# 04-AT86RF215IQ.net
KiCad netlist of a schematic drawn in Altium Designer
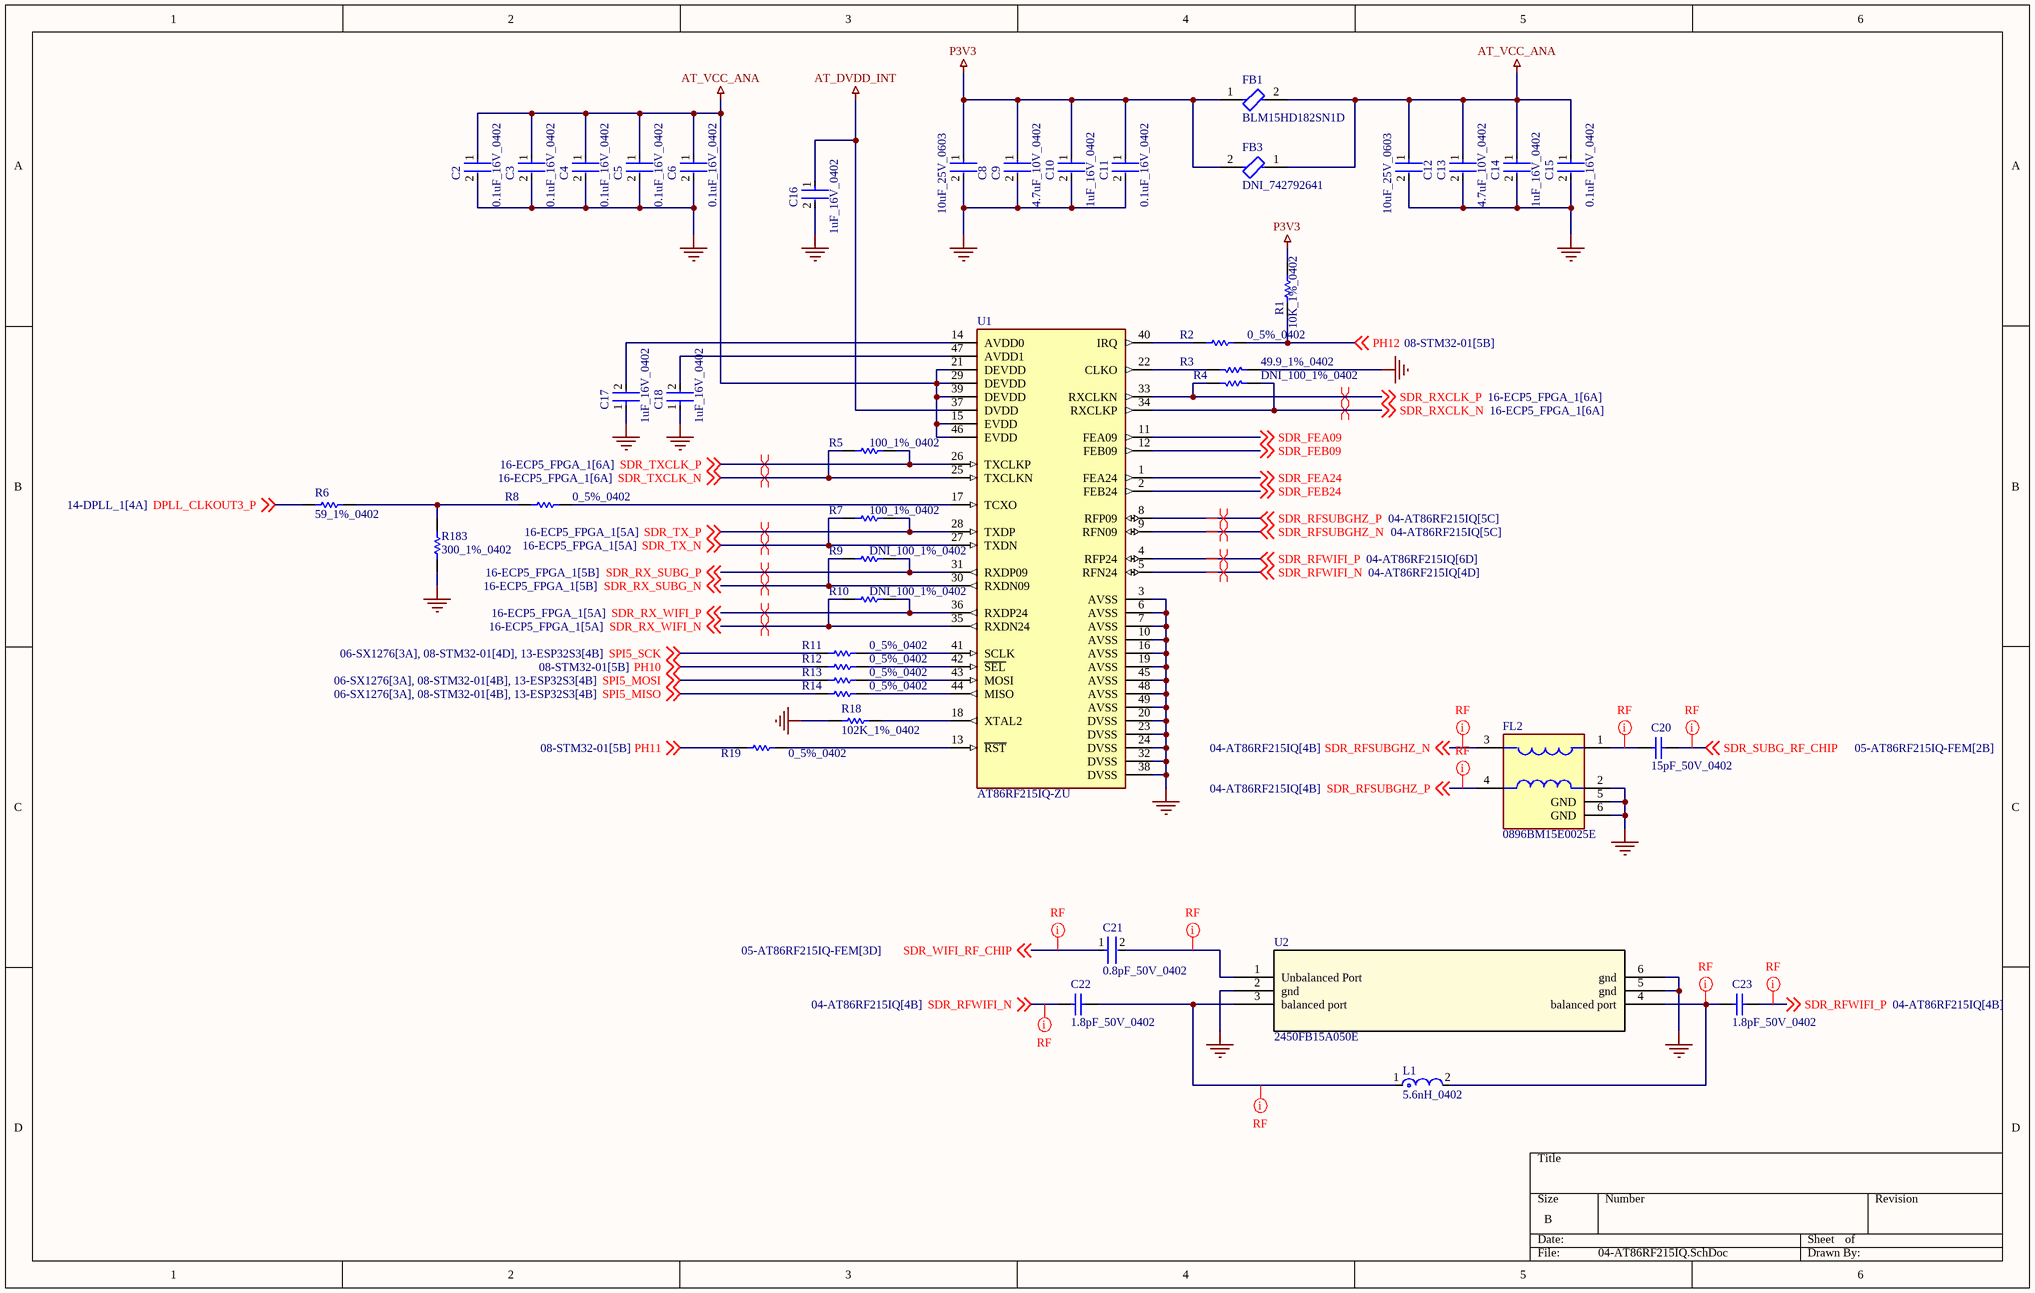
[diagram p0: 04-AT86RF215IQ.SchDoc]

(export (version "E")
  (design (tool "Eeschema 10.0.6"))
  (components
    (comp (ref "C2")
      (value "0.1uF_16V_0402")
      (footprint "FP-C0402-BB-MFG")
      (description "CAP CER 0.1UF 16V 5% X7R 0402")
      (fields
        (field (name "MANUFACTURER") "Kemet")
        (field (name "MANUFACTURER PART NUMBER") "C0402C104J4RACTU")
      )
      (libsource (lib "Altium Content Vault") (part "b4654b650e69147ec39a6b967a45e02"))
    )
    (comp (ref "C3")
      (value "0.1uF_16V_0402")
      (footprint "FP-C0402-BB-MFG")
      (description "CAP CER 0.1UF 16V 5% X7R 0402")
      (fields
        (field (name "MANUFACTURER") "Kemet")
        (field (name "MANUFACTURER PART NUMBER") "C0402C104J4RACTU")
      )
      (libsource (lib "Altium Content Vault") (part "b4654b650e69147ec39a6b967a45e02"))
    )
    (comp (ref "C4")
      (value "0.1uF_16V_0402")
      (footprint "FP-C0402-BB-MFG")
      (description "CAP CER 0.1UF 16V 5% X7R 0402")
      (fields
        (field (name "MANUFACTURER") "Kemet")
        (field (name "MANUFACTURER PART NUMBER") "C0402C104J4RACTU")
      )
      (libsource (lib "Altium Content Vault") (part "b4654b650e69147ec39a6b967a45e02"))
    )
    (comp (ref "C5")
      (value "0.1uF_16V_0402")
      (footprint "FP-C0402-BB-MFG")
      (description "CAP CER 0.1UF 16V 5% X7R 0402")
      (fields
        (field (name "MANUFACTURER") "Kemet")
        (field (name "MANUFACTURER PART NUMBER") "C0402C104J4RACTU")
      )
      (libsource (lib "Altium Content Vault") (part "b4654b650e69147ec39a6b967a45e02"))
    )
    (comp (ref "C6")
      (value "0.1uF_16V_0402")
      (footprint "FP-C0402-BB-MFG")
      (description "CAP CER 0.1UF 16V 5% X7R 0402")
      (fields
        (field (name "MANUFACTURER") "Kemet")
        (field (name "MANUFACTURER PART NUMBER") "C0402C104J4RACTU")
      )
      (libsource (lib "Altium Content Vault") (part "b4654b650e69147ec39a6b967a45e02"))
    )
    (comp (ref "C8")
      (value "10uF_25V_0603")
      (footprint "FP-CL10-IPC_C")
      (description "Cap Ceramic 10uF 25V X5R ±20% Pad SMD 0603 +85°C T/R")
      (fields (field (name "TOLERANCE") "20%"))
      (libsource (lib "Altium Content Vault") (part "b4654b650e69147ec39a6b967a45e02"))
    )
    (comp (ref "C9")
      (value "4.7uF_10V_0402")
      (footprint "FP-C1005-050-0_15-MFG")
      (description "CAP CER 4.7UF 10V X5R 0402")
      (fields (field (name "TOLERANCE") "10%"))
      (libsource (lib "Altium Content Vault") (part "b4654b650e69147ec39a6b967a45e02"))
    )
    (comp (ref "C10")
      (value "1uF_16V_0402")
      (footprint "FP-0402-L_1_0_0_05-W_0_5-IPC_A")
      (description "None")
      (fields (field (name "TOLERANCE") "10%"))
      (libsource (lib "Altium Content Vault") (part "b4654b650e69147ec39a6b967a45e02"))
    )
    (comp (ref "C11")
      (value "0.1uF_16V_0402")
      (footprint "FP-C0402-BB-MFG")
      (description "CAP CER 0.1UF 16V 5% X7R 0402")
      (fields
        (field (name "MANUFACTURER") "Kemet")
        (field (name "MANUFACTURER PART NUMBER") "C0402C104J4RACTU")
      )
      (libsource (lib "Altium Content Vault") (part "b4654b650e69147ec39a6b967a45e02"))
    )
    (comp (ref "C12")
      (value "10uF_25V_0603")
      (footprint "FP-CL10-IPC_C")
      (description "Cap Ceramic 10uF 25V X5R ±20% Pad SMD 0603 +85°C T/R")
      (fields (field (name "TOLERANCE") "20%"))
      (libsource (lib "Altium Content Vault") (part "b4654b650e69147ec39a6b967a45e02"))
    )
    (comp (ref "C13")
      (value "4.7uF_10V_0402")
      (footprint "FP-C1005-050-0_15-MFG")
      (description "CAP CER 4.7UF 10V X5R 0402")
      (fields (field (name "TOLERANCE") "10%"))
      (libsource (lib "Altium Content Vault") (part "b4654b650e69147ec39a6b967a45e02"))
    )
    (comp (ref "C14")
      (value "1uF_16V_0402")
      (footprint "FP-0402-L_1_0_0_05-W_0_5-IPC_A")
      (description "None")
      (fields (field (name "TOLERANCE") "10%"))
      (libsource (lib "Altium Content Vault") (part "b4654b650e69147ec39a6b967a45e02"))
    )
    (comp (ref "C15")
      (value "0.1uF_16V_0402")
      (footprint "FP-C0402-BB-MFG")
      (description "CAP CER 0.1UF 16V 5% X7R 0402")
      (fields
        (field (name "MANUFACTURER") "Kemet")
        (field (name "MANUFACTURER PART NUMBER") "C0402C104J4RACTU")
      )
      (libsource (lib "Altium Content Vault") (part "b4654b650e69147ec39a6b967a45e02"))
    )
    (comp (ref "C16")
      (value "1uF_16V_0402")
      (footprint "FP-0402-L_1_0_0_05-W_0_5-IPC_A")
      (description "None")
      (fields (field (name "TOLERANCE") "10%"))
      (libsource (lib "Altium Content Vault") (part "b4654b650e69147ec39a6b967a45e02"))
    )
    (comp (ref "C17")
      (value "1uF_16V_0402")
      (footprint "FP-0402-L_1_0_0_05-W_0_5-IPC_A")
      (description "None")
      (fields (field (name "TOLERANCE") "10%"))
      (libsource (lib "Altium Content Vault") (part "b4654b650e69147ec39a6b967a45e02"))
    )
    (comp (ref "C18")
      (value "1uF_16V_0402")
      (footprint "FP-0402-L_1_0_0_05-W_0_5-IPC_A")
      (description "None")
      (fields (field (name "TOLERANCE") "10%"))
      (libsource (lib "Altium Content Vault") (part "b4654b650e69147ec39a6b967a45e02"))
    )
    (comp (ref "C20")
      (value "15pF_50V_0402")
      (footprint "CAPC1005X55X25NL05T10")
      (fields (field (name "PART NUMBER") "GRM1555C1H150JZ01D") (field (name "MANUFACTURER") "Murata"))
      (libsource (lib "Altium Content Vault") (part "CAP"))
    )
    (comp (ref "C21")
      (value "0.8pF_50V_0402")
      (footprint "FP-GJM155-0_05-IPC_A")
      (description "Multi-Layer Ceramic Capacitor 0.8pF C0G  ±0.1pF 0402 Paper T/R")
      (fields (field (name "VOLTAGE") "50V"))
      (libsource (lib "Altium Content Vault") (part "02cd4be3c70576c341d710602a673aa"))
    )
    (comp (ref "C22")
      (value "1.8pF_50V_0402")
      (footprint "CAPC1005X55X25LL05T10")
      (fields (field (name "PART NUMBER") "GRM1555C1H1R8CA01D") (field (name "MANUFACTURER") "Murata"))
      (libsource (lib "Altium Content Vault") (part "CAP"))
    )
    (comp (ref "C23")
      (value "1.8pF_50V_0402")
      (footprint "CAPC1005X55X25LL05T10")
      (fields (field (name "PART NUMBER") "GRM1555C1H1R8CA01D") (field (name "MANUFACTURER") "Murata"))
      (libsource (lib "Altium Content Vault") (part "CAP"))
    )
    (comp (ref "FB1")
      (value "BLM15HD182SN1D")
      (footprint "FP-BLM15-0_05-MFG")
      (description "Chip Ferrite Bead, 0402, 1800Ω @ 100MHz, 2.2Ω, 25%, 200mA")
      (fields (field (name "TOLERANCE") "25%"))
      (libsource (lib "Altium Content Vault") (part "5f30dd21d616792df468990f7003faa"))
    )
    (comp (ref "FB3")
      (value "DNI_742792641")
      (footprint "FP-742792641-MFG")
      (description "FERRITE BEAD 300 OHM 0603 1LN")
      (fields (field (name "TOLERANCE") "25%"))
      (libsource (lib "Altium Content Vault") (part "5f30dd21d616792df468990f7003faa"))
    )
    (comp (ref "FL2")
      (value "0896BM15E0025E")
      (footprint "FP-0896BM15E0025E-MFG")
      (description "BALUN 863MHZ-928MHZ 50/50 0805")
      (fields
        (field (name "MANUFACTURER") "Johanson")
        (field (name "OCTOPART") "https://octopart.com/0896bm15e0025e-johanson-71691697")
      )
      (libsource (lib "Altium Content Vault") (part "9725e6fc3b6d4b71249fb6cd7b91a1d"))
    )
    (comp (ref "L1")
      (value "5.6nH_0402")
      (footprint "FP-LQG15HH_02-IPC_A")
      (description "Multilayer type RF Inductor 5.6nH ±0.3nH 0.18Ω 600mA 0402")
      (libsource (lib "Altium Content Vault") (part "4cc4b267dca4c8e51f7102f422741d8"))
    )
    (comp (ref "R1")
      (value "10K_1%_0402")
      (footprint "RESC1005X40X25NL10T10")
      (fields (field (name "MANUFACTURER") "Bourns") (field (name "PART NUMBER") "CR0402-FX-1002GLF"))
      (libsource (lib "Altium Content Vault") (part "RES"))
    )
    (comp (ref "R2")
      (value "0_5%_0402")
      (footprint "RESC1005X40X25NL05T10")
      (fields (field (name "MANUFACTURER") "Panasonic") (field (name "PART NUMBER") "ERJ-U020R00X"))
      (libsource (lib "Altium Content Vault") (part "RES"))
    )
    (comp (ref "R3")
      (value "49.9_1%_0402")
      (footprint "RESC1005X40X25NL10T10")
      (fields (field (name "PART NUMBER") "RK73H1ETTP49R9F") (field (name "MANUFACTURER") "KOA Speer"))
      (libsource (lib "Altium Content Vault") (part "RES"))
    )
    (comp (ref "R4")
      (value "DNI_100_1%_0402")
      (footprint "RESC1005X40X25NL05T10")
      (fields (field (name "MANUFACTURER") "Yageo") (field (name "PART NUMBER") "RC0402FR-13100RL"))
      (libsource (lib "Altium Content Vault") (part "RES"))
    )
    (comp (ref "R5")
      (value "100_1%_0402")
      (footprint "RESC1005X40X25NL05T10")
      (fields (field (name "MANUFACTURER") "Yageo") (field (name "PART NUMBER") "RC0402FR-13100RL"))
      (libsource (lib "Altium Content Vault") (part "RES"))
    )
    (comp (ref "R6")
      (value "59_1%_0402")
      (footprint "RESC1005X40X25ML10T10")
      (fields (field (name "MANUFACTURER") "KOA Speer") (field (name "PART NUMBER") "RK73H1ETTP59R0F"))
      (libsource (lib "Altium Content Vault") (part "RES"))
    )
    (comp (ref "R7")
      (value "100_1%_0402")
      (footprint "RESC1005X40X25NL05T10")
      (fields (field (name "MANUFACTURER") "Yageo") (field (name "PART NUMBER") "RC0402FR-13100RL"))
      (libsource (lib "Altium Content Vault") (part "RES"))
    )
    (comp (ref "R8")
      (value "0_5%_0402")
      (footprint "RESC1005X40X25NL05T10")
      (fields (field (name "MANUFACTURER") "Panasonic") (field (name "PART NUMBER") "ERJ-U020R00X"))
      (libsource (lib "Altium Content Vault") (part "RES"))
    )
    (comp (ref "R9")
      (value "DNI_100_1%_0402")
      (footprint "RESC1005X40X25NL05T10")
      (fields (field (name "MANUFACTURER") "Yageo") (field (name "PART NUMBER") "RC0402FR-13100RL"))
      (libsource (lib "Altium Content Vault") (part "RES"))
    )
    (comp (ref "R10")
      (value "DNI_100_1%_0402")
      (footprint "RESC1005X40X25NL05T10")
      (fields (field (name "MANUFACTURER") "Yageo") (field (name "PART NUMBER") "RC0402FR-13100RL"))
      (libsource (lib "Altium Content Vault") (part "RES"))
    )
    (comp (ref "R11")
      (value "0_5%_0402")
      (footprint "RESC1005X40X25NL05T10")
      (fields (field (name "MANUFACTURER") "Panasonic") (field (name "PART NUMBER") "ERJ-U020R00X"))
      (libsource (lib "Altium Content Vault") (part "RES"))
    )
    (comp (ref "R12")
      (value "0_5%_0402")
      (footprint "RESC1005X40X25NL05T10")
      (fields (field (name "MANUFACTURER") "Panasonic") (field (name "PART NUMBER") "ERJ-U020R00X"))
      (libsource (lib "Altium Content Vault") (part "RES"))
    )
    (comp (ref "R13")
      (value "0_5%_0402")
      (footprint "RESC1005X40X25NL05T10")
      (fields (field (name "MANUFACTURER") "Panasonic") (field (name "PART NUMBER") "ERJ-U020R00X"))
      (libsource (lib "Altium Content Vault") (part "RES"))
    )
    (comp (ref "R14")
      (value "0_5%_0402")
      (footprint "RESC1005X40X25NL05T10")
      (fields (field (name "MANUFACTURER") "Panasonic") (field (name "PART NUMBER") "ERJ-U020R00X"))
      (libsource (lib "Altium Content Vault") (part "RES"))
    )
    (comp (ref "R18")
      (value "102K_1%_0402")
      (footprint "RESC1005X40X25ML05T10")
      (fields (field (name "MANUFACTURER") "Yageo") (field (name "PART NUMBER") "RC0402FR-07102KL"))
      (libsource (lib "Altium Content Vault") (part "RES"))
    )
    (comp (ref "R19")
      (value "0_5%_0402")
      (footprint "RESC1005X40X25NL05T10")
      (fields (field (name "MANUFACTURER") "Panasonic") (field (name "PART NUMBER") "ERJ-U020R00X"))
      (libsource (lib "Altium Content Vault") (part "RES"))
    )
    (comp (ref "R183")
      (value "300_1%_0402")
      (footprint "RESC1005X40X25LL10T10")
      (fields (field (name "PART NUMBER") "MC00625W04021300R") (field (name "MANUFACTURER") "Multicomp"))
      (libsource (lib "Altium Content Vault") (part "RES"))
    )
    (comp (ref "U1")
      (value "AT86RF215IQ-ZU")
      (footprint "FP-AT86RF215IQ-ZU-MFG")
      (description "IC RF TXRX 802.15.4 48VFQFN")
      (fields
        (field (name "MANUFACTURER") "Microchip")
        (field (name "OCTOPART") "https://octopart.com/at86rf215iq-zu-microchip-77758620")
      )
      (libsource (lib "Altium Content Vault") (part "c531c0ad6565c2a43c7312791734b45"))
    )
    (comp (ref "U2")
      (value "2450FB15A050E")
      (footprint "2450FB15A050E_JOT")
      (description "No Description Available")
      (libsource (lib "2450FB15A050E") (part "2450FB15A050E"))
    )
  )
  (nets
    (net (code "1") (name "AT_DVDD_INT") (class "Default")
      (node (ref "C16") (pin "1") (pinfunction "1_1") (pintype "passive"))
      (node (ref "U1") (pin "37") (pinfunction "DVDD_37") (pintype "power_in"))
    )
    (net (code "2") (name "AT_VCC_ANA") (class "Default")
      (node (ref "C12") (pin "1") (pinfunction "1_1") (pintype "passive"))
      (node (ref "C13") (pin "1") (pinfunction "1_1") (pintype "passive"))
      (node (ref "C14") (pin "1") (pinfunction "1_1") (pintype "passive"))
      (node (ref "C15") (pin "1") (pinfunction "1_1") (pintype "passive"))
      (node (ref "C2") (pin "1") (pinfunction "1_1") (pintype "passive"))
      (node (ref "C3") (pin "1") (pinfunction "1_1") (pintype "passive"))
      (node (ref "C4") (pin "1") (pinfunction "1_1") (pintype "passive"))
      (node (ref "C5") (pin "1") (pinfunction "1_1") (pintype "passive"))
      (node (ref "C6") (pin "1") (pinfunction "1_1") (pintype "passive"))
      (node (ref "FB1") (pin "2") (pinfunction "2_2") (pintype "passive"))
      (node (ref "FB3") (pin "1") (pinfunction "1_1") (pintype "passive"))
      (node (ref "U1") (pin "15") (pinfunction "EVDD_15") (pintype "power_in"))
      (node (ref "U1") (pin "21") (pinfunction "DEVDD_21") (pintype "power_in"))
      (node (ref "U1") (pin "29") (pinfunction "DEVDD_29") (pintype "power_in"))
      (node (ref "U1") (pin "39") (pinfunction "DEVDD_39") (pintype "power_in"))
      (node (ref "U1") (pin "46") (pinfunction "EVDD_46") (pintype "power_in"))
    )
    (net (code "3") (name "DPLL_CLKOUT3_P") (class "Default")
      (node (ref "R6") (pin "1") (pinfunction "1_1") (pintype "passive"))
    )
    (net (code "4") (name "GND") (class "Default")
      (node (ref "C10") (pin "2") (pinfunction "2_2") (pintype "passive"))
      (node (ref "C11") (pin "2") (pinfunction "2_2") (pintype "passive"))
      (node (ref "C12") (pin "2") (pinfunction "2_2") (pintype "passive"))
      (node (ref "C13") (pin "2") (pinfunction "2_2") (pintype "passive"))
      (node (ref "C14") (pin "2") (pinfunction "2_2") (pintype "passive"))
      (node (ref "C15") (pin "2") (pinfunction "2_2") (pintype "passive"))
      (node (ref "C16") (pin "2") (pinfunction "2_2") (pintype "passive"))
      (node (ref "C17") (pin "1") (pinfunction "1_1") (pintype "passive"))
      (node (ref "C18") (pin "1") (pinfunction "1_1") (pintype "passive"))
      (node (ref "C2") (pin "2") (pinfunction "2_2") (pintype "passive"))
      (node (ref "C3") (pin "2") (pinfunction "2_2") (pintype "passive"))
      (node (ref "C4") (pin "2") (pinfunction "2_2") (pintype "passive"))
      (node (ref "C5") (pin "2") (pinfunction "2_2") (pintype "passive"))
      (node (ref "C6") (pin "2") (pinfunction "2_2") (pintype "passive"))
      (node (ref "C8") (pin "2") (pinfunction "2_2") (pintype "passive"))
      (node (ref "C9") (pin "2") (pinfunction "2_2") (pintype "passive"))
      (node (ref "FL2") (pin "2") (pinfunction "GND_2") (pintype "power_in"))
      (node (ref "FL2") (pin "5") (pinfunction "GND_5") (pintype "power_in"))
      (node (ref "FL2") (pin "6") (pinfunction "GND_6") (pintype "power_in"))
      (node (ref "R18") (pin "1") (pinfunction "1_1") (pintype "passive"))
      (node (ref "R183") (pin "1") (pinfunction "1_1") (pintype "passive"))
      (node (ref "R3") (pin "2") (pinfunction "2_2") (pintype "passive"))
      (node (ref "U1") (pin "10") (pinfunction "AVSS_10") (pintype "power_in"))
      (node (ref "U1") (pin "16") (pinfunction "AVSS_16") (pintype "power_in"))
      (node (ref "U1") (pin "19") (pinfunction "AVSS_19") (pintype "power_in"))
      (node (ref "U1") (pin "20") (pinfunction "DVSS_20") (pintype "power_in"))
      (node (ref "U1") (pin "23") (pinfunction "DVSS_23") (pintype "power_in"))
      (node (ref "U1") (pin "24") (pinfunction "DVSS_24") (pintype "power_in"))
      (node (ref "U1") (pin "3") (pinfunction "AVSS_3") (pintype "power_in"))
      (node (ref "U1") (pin "32") (pinfunction "DVSS_32") (pintype "power_in"))
      (node (ref "U1") (pin "38") (pinfunction "DVSS_38") (pintype "power_in"))
      (node (ref "U1") (pin "45") (pinfunction "AVSS_45") (pintype "power_in"))
      (node (ref "U1") (pin "48") (pinfunction "AVSS_48") (pintype "power_in"))
      (node (ref "U1") (pin "49") (pinfunction "AVSS_49") (pintype "power_in"))
      (node (ref "U1") (pin "6") (pinfunction "AVSS_6") (pintype "power_in"))
      (node (ref "U1") (pin "7") (pinfunction "AVSS_7") (pintype "power_in"))
      (node (ref "U2") (pin "2") (pinfunction "gnd_2") (pintype "passive"))
      (node (ref "U2") (pin "5") (pinfunction "gnd_5") (pintype "passive"))
      (node (ref "U2") (pin "6") (pinfunction "gnd_6") (pintype "passive"))
    )
    (net (code "5") (name "Net-(C22-Pad2)") (class "Default")
      (node (ref "C22") (pin "2") (pinfunction "2_2") (pintype "passive"))
      (node (ref "L1") (pin "1") (pinfunction "1_1") (pintype "passive"))
      (node (ref "U2") (pin "3") (pinfunction "balanced_port_3") (pintype "passive"))
    )
    (net (code "6") (name "Net-(C23-Pad1)") (class "Default")
      (node (ref "C23") (pin "1") (pinfunction "1_1") (pintype "passive"))
      (node (ref "L1") (pin "2") (pinfunction "2_2") (pintype "passive"))
      (node (ref "U2") (pin "4") (pinfunction "balanced_port_4") (pintype "passive"))
    )
    (net (code "7") (name "Net-(FL2-Unbalanced_Port)") (class "Default")
      (node (ref "C20") (pin "1") (pinfunction "1_1") (pintype "passive"))
      (node (ref "FL2") (pin "1") (pinfunction "Unbalanced_Port_1") (pintype "passive"))
    )
    (net (code "8") (name "Net-(R183-Pad2)") (class "Default")
      (node (ref "R183") (pin "2") (pinfunction "2_2") (pintype "passive"))
      (node (ref "R6") (pin "2") (pinfunction "2_2") (pintype "passive"))
      (node (ref "R8") (pin "1") (pinfunction "1_1") (pintype "passive"))
    )
    (net (code "9") (name "Net-(U1-AVDD0)") (class "Default")
      (node (ref "C17") (pin "2") (pinfunction "2_2") (pintype "passive"))
      (node (ref "U1") (pin "14") (pinfunction "AVDD0_14") (pintype "power_in"))
    )
    (net (code "10") (name "Net-(U1-AVDD1)") (class "Default")
      (node (ref "C18") (pin "2") (pinfunction "2_2") (pintype "passive"))
      (node (ref "U1") (pin "47") (pinfunction "AVDD1_47") (pintype "power_in"))
    )
    (net (code "11") (name "Net-(U1-CLKO)") (class "Default")
      (node (ref "R3") (pin "1") (pinfunction "1_1") (pintype "passive"))
      (node (ref "U1") (pin "22") (pinfunction "CLKO_22") (pintype "output"))
    )
    (net (code "12") (name "Net-(U1-IRQ)") (class "Default")
      (node (ref "R2") (pin "1") (pinfunction "1_1") (pintype "passive"))
      (node (ref "U1") (pin "40") (pinfunction "IRQ_40") (pintype "output"))
    )
    (net (code "13") (name "Net-(U1-MISO)") (class "Default")
      (node (ref "R14") (pin "2") (pinfunction "2_2") (pintype "passive"))
      (node (ref "U1") (pin "44") (pinfunction "MISO_44") (pintype "output"))
    )
    (net (code "14") (name "Net-(U1-MOSI)") (class "Default")
      (node (ref "R13") (pin "2") (pinfunction "2_2") (pintype "passive"))
      (node (ref "U1") (pin "43") (pinfunction "MOSI_43") (pintype "input"))
    )
    (net (code "15") (name "Net-(U1-SCLK)") (class "Default")
      (node (ref "R11") (pin "2") (pinfunction "2_2") (pintype "passive"))
      (node (ref "U1") (pin "41") (pinfunction "SCLK_41") (pintype "input"))
    )
    (net (code "16") (name "Net-(U1-TCXO)") (class "Default")
      (node (ref "R8") (pin "2") (pinfunction "2_2") (pintype "passive"))
      (node (ref "U1") (pin "17") (pinfunction "TCXO_17") (pintype "input"))
    )
    (net (code "17") (name "Net-(U1-XTAL2)") (class "Default")
      (node (ref "R18") (pin "2") (pinfunction "2_2") (pintype "passive"))
      (node (ref "U1") (pin "18") (pinfunction "XTAL2_18") (pintype "output"))
    )
    (net (code "18") (name "Net-(U1-~{RST})") (class "Default")
      (node (ref "R19") (pin "2") (pinfunction "2_2") (pintype "passive"))
      (node (ref "U1") (pin "13") (pinfunction "~{RST}_13") (pintype "input"))
    )
    (net (code "19") (name "Net-(U1-~{SEL})") (class "Default")
      (node (ref "R12") (pin "2") (pinfunction "2_2") (pintype "passive"))
      (node (ref "U1") (pin "42") (pinfunction "~{SEL}_42") (pintype "input"))
    )
    (net (code "20") (name "Net-(U2-Unbalanced_Port)") (class "Default")
      (node (ref "C21") (pin "2") (pinfunction "2_2") (pintype "passive"))
      (node (ref "U2") (pin "1") (pinfunction "Unbalanced_Port_1") (pintype "passive"))
    )
    (net (code "21") (name "P3V3") (class "Default")
      (node (ref "C10") (pin "1") (pinfunction "1_1") (pintype "passive"))
      (node (ref "C11") (pin "1") (pinfunction "1_1") (pintype "passive"))
      (node (ref "C8") (pin "1") (pinfunction "1_1") (pintype "passive"))
      (node (ref "C9") (pin "1") (pinfunction "1_1") (pintype "passive"))
      (node (ref "FB1") (pin "1") (pinfunction "1_1") (pintype "passive"))
      (node (ref "FB3") (pin "2") (pinfunction "2_2") (pintype "passive"))
      (node (ref "R1") (pin "2") (pinfunction "2_2") (pintype "passive"))
    )
    (net (code "22") (name "PH10") (class "Default")
      (node (ref "R12") (pin "1") (pinfunction "1_1") (pintype "passive"))
    )
    (net (code "23") (name "PH11") (class "Default")
      (node (ref "R19") (pin "1") (pinfunction "1_1") (pintype "passive"))
    )
    (net (code "24") (name "PH12") (class "Default")
      (node (ref "R1") (pin "1") (pinfunction "1_1") (pintype "passive"))
      (node (ref "R2") (pin "2") (pinfunction "2_2") (pintype "passive"))
    )
    (net (code "25") (name "SDR_FEA09") (class "Default")
      (node (ref "U1") (pin "11") (pinfunction "FEA09_11") (pintype "output"))
    )
    (net (code "26") (name "SDR_FEA24") (class "Default")
      (node (ref "U1") (pin "1") (pinfunction "FEA24_1") (pintype "output"))
    )
    (net (code "27") (name "SDR_FEB09") (class "Default")
      (node (ref "U1") (pin "12") (pinfunction "FEB09_12") (pintype "output"))
    )
    (net (code "28") (name "SDR_FEB24") (class "Default")
      (node (ref "U1") (pin "2") (pinfunction "FEB24_2") (pintype "output"))
    )
    (net (code "29") (name "SDR_RFSUBGHZ_N") (class "Default")
      (node (ref "FL2") (pin "3") (pinfunction "1_Balanced_Port_3") (pintype "passive"))
      (node (ref "U1") (pin "9") (pinfunction "RFN09_9") (pintype "bidirectional"))
    )
    (net (code "30") (name "SDR_RFSUBGHZ_P") (class "Default")
      (node (ref "FL2") (pin "4") (pinfunction "2_Balanced_Port_4") (pintype "passive"))
      (node (ref "U1") (pin "8") (pinfunction "RFP09_8") (pintype "bidirectional"))
    )
    (net (code "31") (name "SDR_RFWIFI_N") (class "Default")
      (node (ref "C22") (pin "1") (pinfunction "1_1") (pintype "passive"))
      (node (ref "U1") (pin "5") (pinfunction "RFN24_5") (pintype "bidirectional"))
    )
    (net (code "32") (name "SDR_RFWIFI_P") (class "Default")
      (node (ref "C23") (pin "2") (pinfunction "2_2") (pintype "passive"))
      (node (ref "U1") (pin "4") (pinfunction "RFP24_4") (pintype "bidirectional"))
    )
    (net (code "33") (name "SDR_RXCLK_N") (class "Default")
      (node (ref "R4") (pin "1") (pinfunction "1_1") (pintype "passive"))
      (node (ref "U1") (pin "34") (pinfunction "RXCLKP_34") (pintype "output"))
    )
    (net (code "34") (name "SDR_RXCLK_P") (class "Default")
      (node (ref "R4") (pin "2") (pinfunction "2_2") (pintype "passive"))
      (node (ref "U1") (pin "33") (pinfunction "RXCLKN_33") (pintype "output"))
    )
    (net (code "35") (name "SDR_RX_SUBG_N") (class "Default")
      (node (ref "R9") (pin "1") (pinfunction "1_1") (pintype "passive"))
      (node (ref "U1") (pin "30") (pinfunction "RXDN09_30") (pintype "output"))
    )
    (net (code "36") (name "SDR_RX_SUBG_P") (class "Default")
      (node (ref "R9") (pin "2") (pinfunction "2_2") (pintype "passive"))
      (node (ref "U1") (pin "31") (pinfunction "RXDP09_31") (pintype "output"))
    )
    (net (code "37") (name "SDR_RX_WIFI_N") (class "Default")
      (node (ref "R10") (pin "1") (pinfunction "1_1") (pintype "passive"))
      (node (ref "U1") (pin "35") (pinfunction "RXDN24_35") (pintype "output"))
    )
    (net (code "38") (name "SDR_RX_WIFI_P") (class "Default")
      (node (ref "R10") (pin "2") (pinfunction "2_2") (pintype "passive"))
      (node (ref "U1") (pin "36") (pinfunction "RXDP24_36") (pintype "output"))
    )
    (net (code "39") (name "SDR_SUBG_RF_CHIP") (class "Default")
      (node (ref "C20") (pin "2") (pinfunction "2_2") (pintype "passive"))
    )
    (net (code "40") (name "SDR_TXCLK_N") (class "Default")
      (node (ref "R5") (pin "1") (pinfunction "1_1") (pintype "passive"))
      (node (ref "U1") (pin "25") (pinfunction "TXCLKN_25") (pintype "input"))
    )
    (net (code "41") (name "SDR_TXCLK_P") (class "Default")
      (node (ref "R5") (pin "2") (pinfunction "2_2") (pintype "passive"))
      (node (ref "U1") (pin "26") (pinfunction "TXCLKP_26") (pintype "input"))
    )
    (net (code "42") (name "SDR_TX_N") (class "Default")
      (node (ref "R7") (pin "1") (pinfunction "1_1") (pintype "passive"))
      (node (ref "U1") (pin "27") (pinfunction "TXDN_27") (pintype "input"))
    )
    (net (code "43") (name "SDR_TX_P") (class "Default")
      (node (ref "R7") (pin "2") (pinfunction "2_2") (pintype "passive"))
      (node (ref "U1") (pin "28") (pinfunction "TXDP_28") (pintype "input"))
    )
    (net (code "44") (name "SDR_WIFI_RF_CHIP") (class "Default")
      (node (ref "C21") (pin "1") (pinfunction "1_1") (pintype "passive"))
    )
    (net (code "45") (name "SPI5_MISO") (class "Default")
      (node (ref "R14") (pin "1") (pinfunction "1_1") (pintype "passive"))
    )
    (net (code "46") (name "SPI5_MOSI") (class "Default")
      (node (ref "R13") (pin "1") (pinfunction "1_1") (pintype "passive"))
    )
    (net (code "47") (name "SPI5_SCK") (class "Default")
      (node (ref "R11") (pin "1") (pinfunction "1_1") (pintype "passive"))
    )
  )
)
